# ConversorRS485.net
KiCad netlist of a schematic drawn in Altium Designer
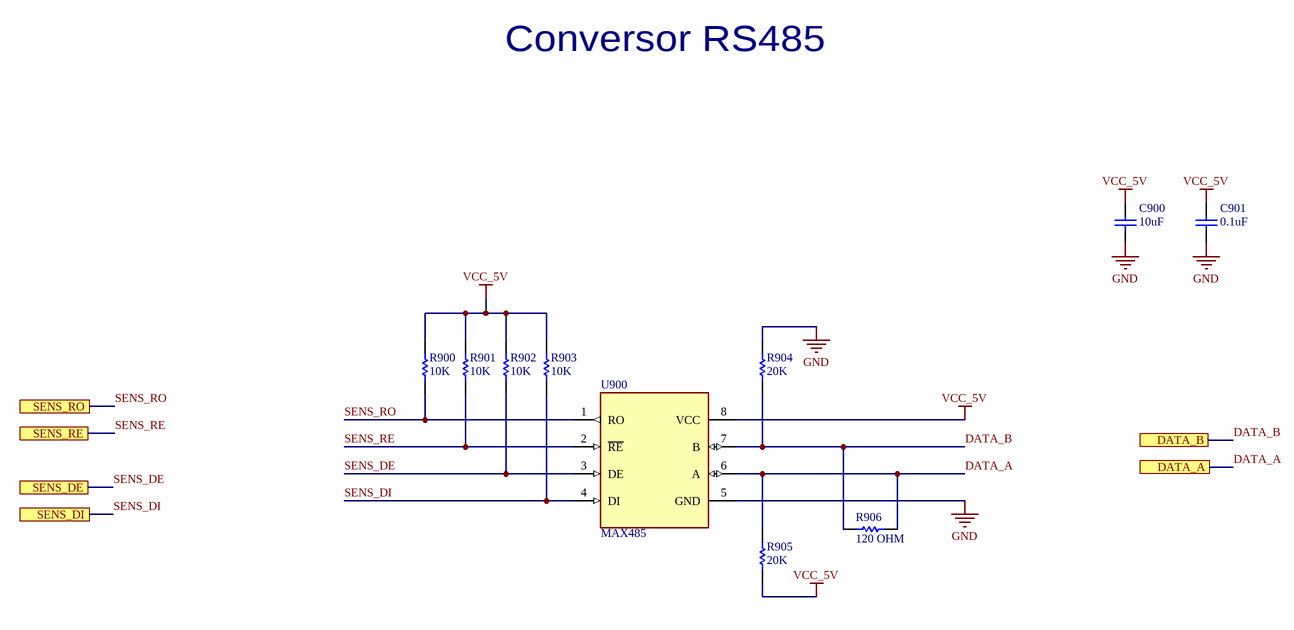
[diagram p0: ConversorRS485.SchDoc]

(export (version "E")
  (design (tool "Eeschema 10.0.6"))
  (components
    (comp (ref "C900")
      (value "10uF")
      (footprint "CAP_CER_0805")
      (libsource (lib "PCB_TCC") (part "CAP_CER_10uF_0805"))
    )
    (comp (ref "C901")
      (value "0.1uF")
      (footprint "CAP_CER_0603")
      (libsource (lib "PCB_TCC") (part "CAP_CER_0.1uF_0603"))
    )
    (comp (ref "R900") (value "10K") (footprint "RES_0603") (libsource (lib "PCB_TCC") (part "RES_10K_0603")))
    (comp (ref "R901") (value "10K") (footprint "RES_0603") (libsource (lib "PCB_TCC") (part "RES_10K_0603")))
    (comp (ref "R902") (value "10K") (footprint "RES_0603") (libsource (lib "PCB_TCC") (part "RES_10K_0603")))
    (comp (ref "R903") (value "10K") (footprint "RES_0603") (libsource (lib "PCB_TCC") (part "RES_10K_0603")))
    (comp (ref "R904") (value "20K") (footprint "RES_0603") (libsource (lib "PCB_TCC") (part "RES_20K_0603")))
    (comp (ref "R905") (value "20K") (footprint "RES_0603") (libsource (lib "PCB_TCC") (part "RES_20K_0603")))
    (comp (ref "R906")
      (value "120 OHM")
      (footprint "RES_0603")
      (libsource (lib "PCB_TCC") (part "RES_120OHM_0603"))
    )
    (comp (ref "U900") (value "MAX485") (footprint "MAX485") (libsource (lib "PCB_TCC") (part "MAX485")))
  )
  (nets
    (net (code "1") (name "/DATA_A") (class "Default")
      (node (ref "R905") (pin "2") (pinfunction "2_2") (pintype "passive"))
      (node (ref "R906") (pin "2") (pinfunction "2_2") (pintype "passive"))
      (node (ref "U900") (pin "6") (pinfunction "A_6") (pintype "bidirectional"))
    )
    (net (code "2") (name "/DATA_B") (class "Default")
      (node (ref "R904") (pin "1") (pinfunction "1_1") (pintype "passive"))
      (node (ref "R906") (pin "1") (pinfunction "1_1") (pintype "passive"))
      (node (ref "U900") (pin "7") (pinfunction "B_7") (pintype "bidirectional"))
    )
    (net (code "3") (name "/SENS_DE") (class "Default")
      (node (ref "R902") (pin "1") (pinfunction "1_1") (pintype "passive"))
      (node (ref "U900") (pin "3") (pinfunction "DE_3") (pintype "input"))
    )
    (net (code "4") (name "/SENS_DI") (class "Default")
      (node (ref "R903") (pin "1") (pinfunction "1_1") (pintype "passive"))
      (node (ref "U900") (pin "4") (pinfunction "DI_4") (pintype "input"))
    )
    (net (code "5") (name "/SENS_RE") (class "Default")
      (node (ref "R901") (pin "1") (pinfunction "1_1") (pintype "passive"))
      (node (ref "U900") (pin "2") (pinfunction "~{RE}_2") (pintype "input"))
    )
    (net (code "6") (name "/SENS_RO") (class "Default")
      (node (ref "R900") (pin "1") (pinfunction "1_1") (pintype "passive"))
      (node (ref "U900") (pin "1") (pinfunction "RO_1") (pintype "output"))
    )
    (net (code "7") (name "GND") (class "Default")
      (node (ref "C900") (pin "2") (pinfunction "2_2") (pintype "passive"))
      (node (ref "C901") (pin "1") (pinfunction "1_1") (pintype "passive"))
      (node (ref "R904") (pin "2") (pinfunction "2_2") (pintype "passive"))
      (node (ref "U900") (pin "5") (pinfunction "GND_5") (pintype "power_in"))
    )
    (net (code "8") (name "VCC_5V") (class "Default")
      (node (ref "C900") (pin "1") (pinfunction "1_1") (pintype "passive"))
      (node (ref "C901") (pin "2") (pinfunction "2_2") (pintype "passive"))
      (node (ref "R900") (pin "2") (pinfunction "2_2") (pintype "passive"))
      (node (ref "R901") (pin "2") (pinfunction "2_2") (pintype "passive"))
      (node (ref "R902") (pin "2") (pinfunction "2_2") (pintype "passive"))
      (node (ref "R903") (pin "2") (pinfunction "2_2") (pintype "passive"))
      (node (ref "R905") (pin "1") (pinfunction "1_1") (pintype "passive"))
      (node (ref "U900") (pin "8") (pinfunction "VCC_8") (pintype "power_in"))
    )
  )
)
